# base-board.net
KiCad netlist of a schematic drawn in EAGLE
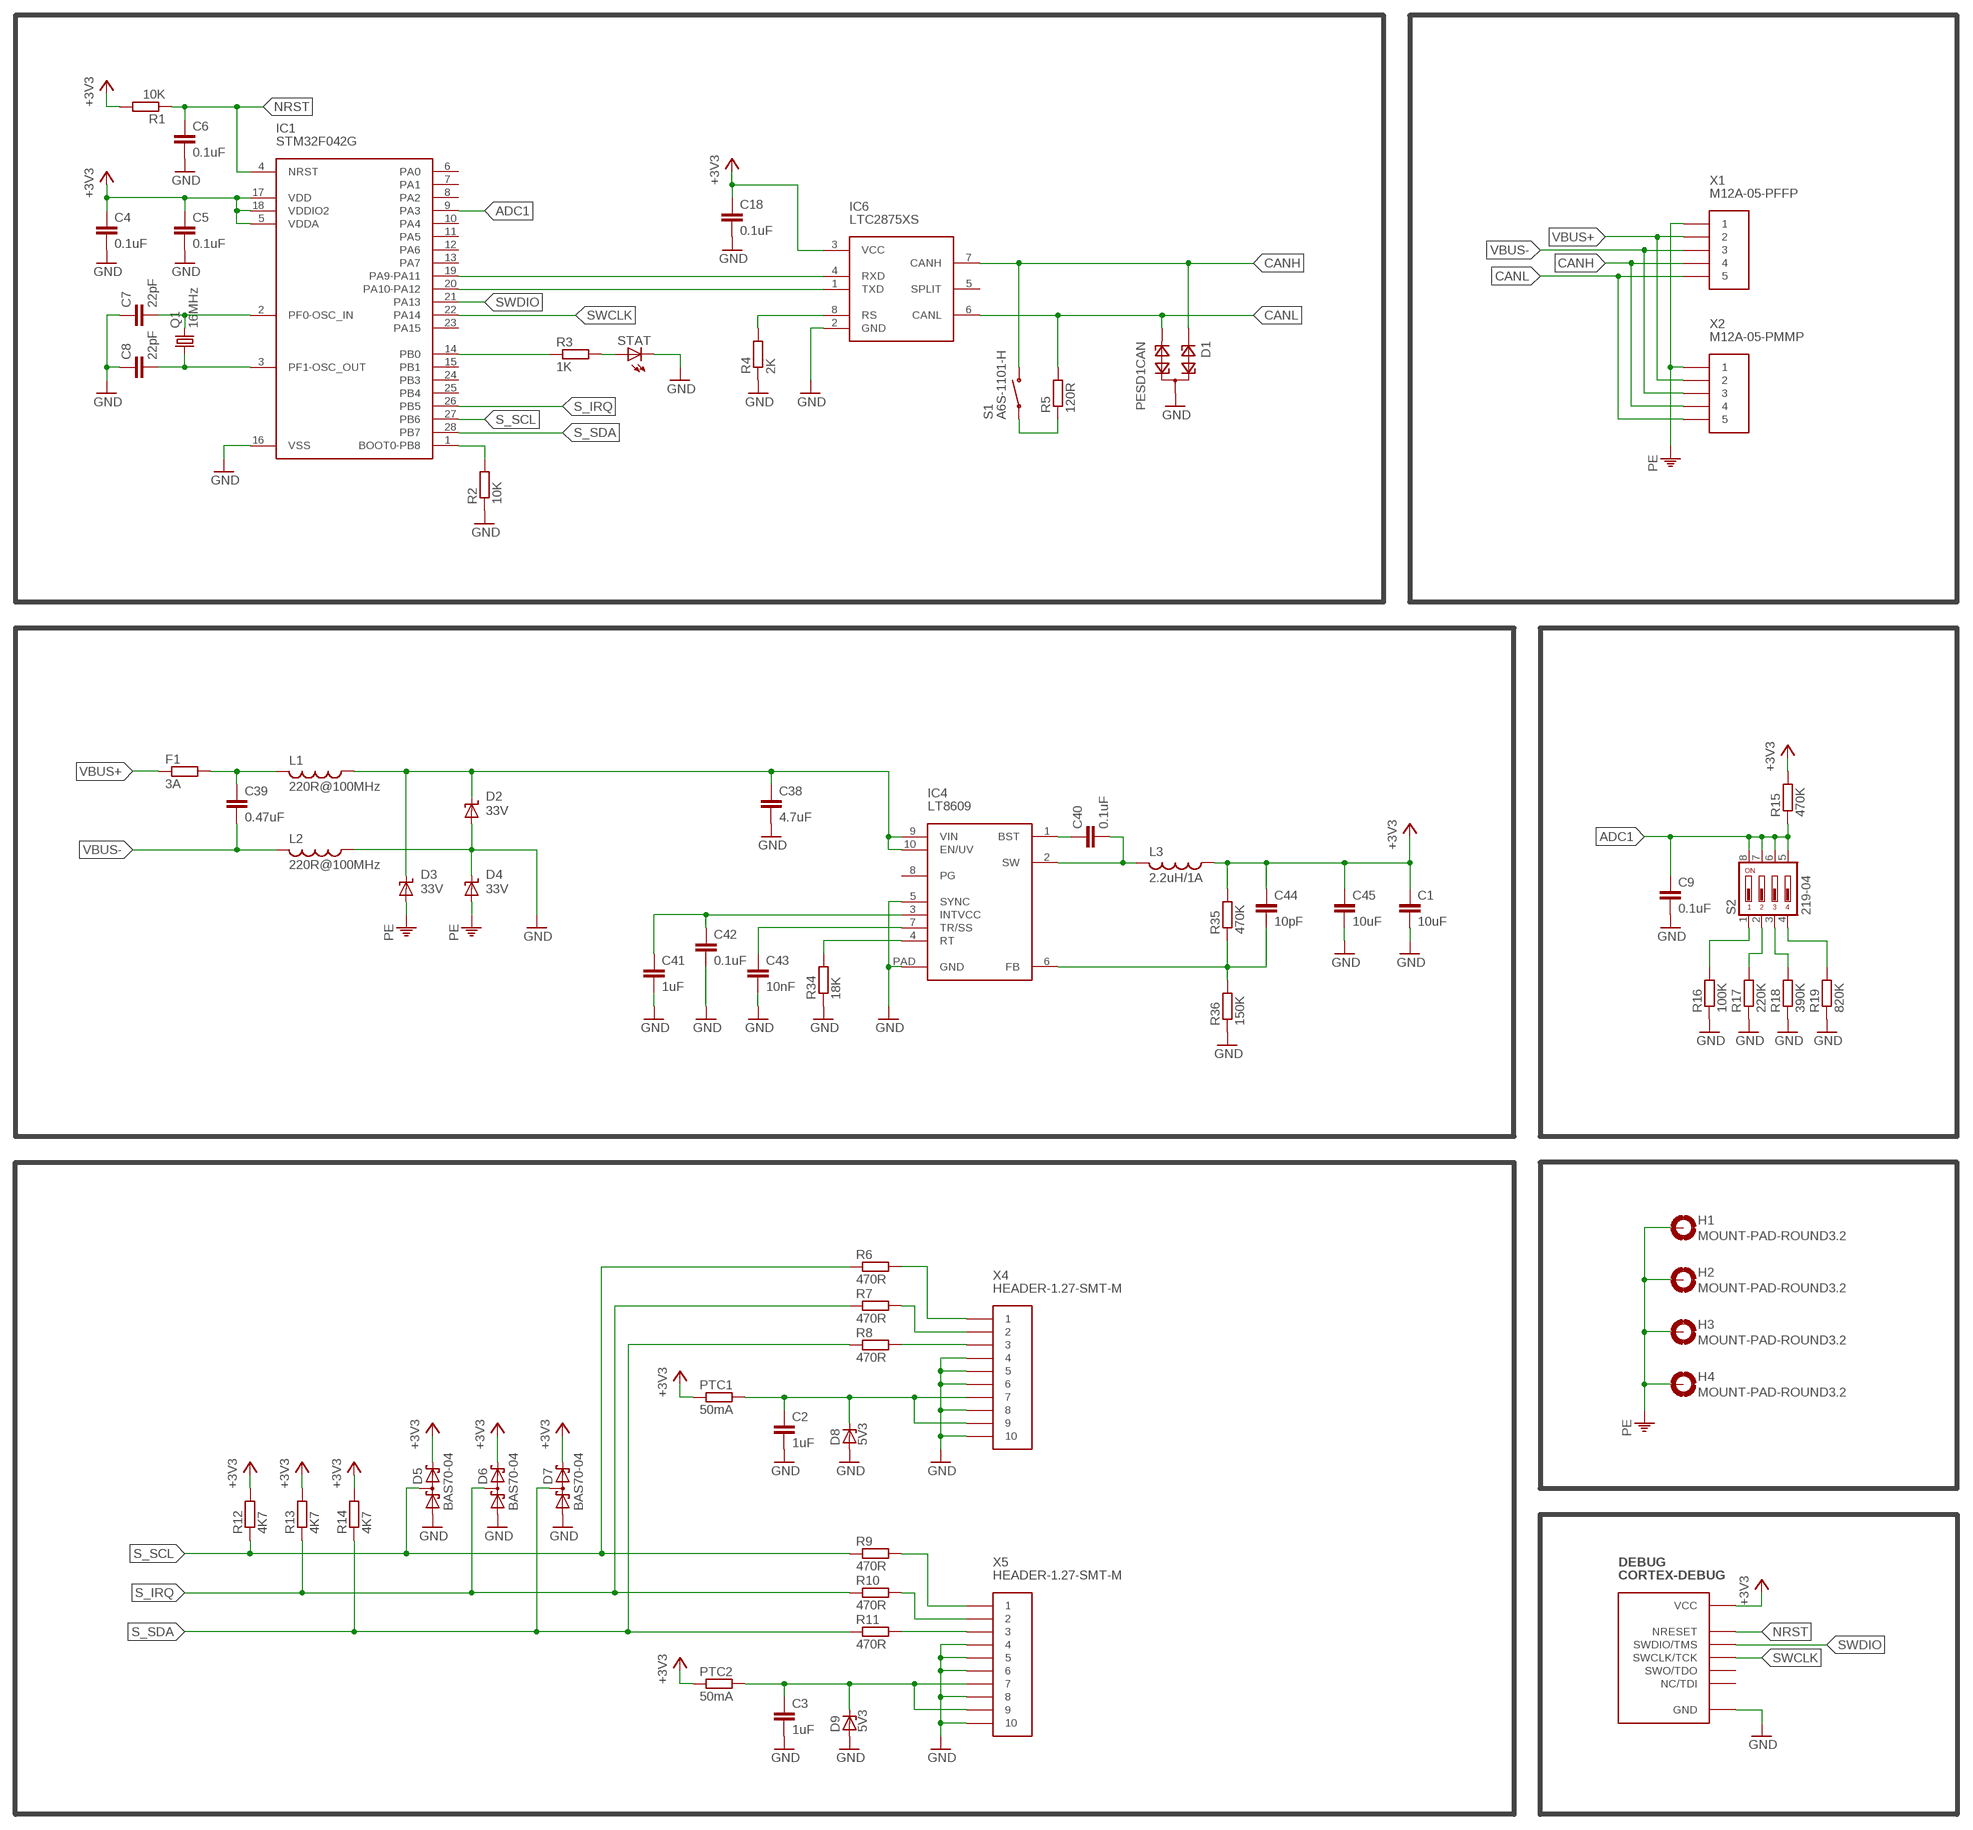
[diagram p0: schematic, sheet 1]

(export (version "E")
  (design (tool "Eeschema 10.0.6"))
  (components
    (comp (ref "C1")
      (value "10uF")
      (footprint "eagle-import:C1206")
      (libsource (lib "eagle-import") (part "C-EUC1206"))
    )
    (comp (ref "C2")
      (value "1uF")
      (footprint "eagle-import:C0603")
      (libsource (lib "eagle-import") (part "C-EUC0603"))
    )
    (comp (ref "C3")
      (value "1uF")
      (footprint "eagle-import:C0603")
      (libsource (lib "eagle-import") (part "C-EUC0603"))
    )
    (comp (ref "C4")
      (value "0.1uF")
      (footprint "eagle-import:C0603")
      (libsource (lib "eagle-import") (part "C-EUC0603"))
    )
    (comp (ref "C5")
      (value "0.1uF")
      (footprint "eagle-import:C0603")
      (libsource (lib "eagle-import") (part "C-EUC0603"))
    )
    (comp (ref "C6")
      (value "0.1uF")
      (footprint "eagle-import:C0603")
      (libsource (lib "eagle-import") (part "C-EUC0603"))
    )
    (comp (ref "C7")
      (value "22pF")
      (footprint "eagle-import:C0603")
      (libsource (lib "eagle-import") (part "C-EUC0603"))
    )
    (comp (ref "C8")
      (value "22pF")
      (footprint "eagle-import:C0603")
      (libsource (lib "eagle-import") (part "C-EUC0603"))
    )
    (comp (ref "C9")
      (value "0.1uF")
      (footprint "eagle-import:C0603")
      (libsource (lib "eagle-import") (part "C-EUC0603"))
    )
    (comp (ref "C18")
      (value "0.1uF")
      (footprint "eagle-import:C0603")
      (libsource (lib "eagle-import") (part "C-EUC0603"))
    )
    (comp (ref "C38")
      (value "4.7uF")
      (footprint "eagle-import:C1206")
      (libsource (lib "eagle-import") (part "C-EUC1206"))
    )
    (comp (ref "C39")
      (value "0.47uF")
      (footprint "eagle-import:C1206")
      (libsource (lib "eagle-import") (part "C-EUC1206"))
    )
    (comp (ref "C40")
      (value "0.1uF")
      (footprint "eagle-import:C0603")
      (libsource (lib "eagle-import") (part "C-EUC0603"))
    )
    (comp (ref "C41")
      (value "1uF")
      (footprint "eagle-import:C0603")
      (libsource (lib "eagle-import") (part "C-EUC0603"))
    )
    (comp (ref "C42")
      (value "0.1uF")
      (footprint "eagle-import:C0603")
      (libsource (lib "eagle-import") (part "C-EUC0603"))
    )
    (comp (ref "C43")
      (value "10nF")
      (footprint "eagle-import:C0603")
      (libsource (lib "eagle-import") (part "C-EUC0603"))
    )
    (comp (ref "C44")
      (value "10pF")
      (footprint "eagle-import:C0603")
      (libsource (lib "eagle-import") (part "C-EUC0603"))
    )
    (comp (ref "C45")
      (value "10uF")
      (footprint "eagle-import:C1206")
      (libsource (lib "eagle-import") (part "C-EUC1206"))
    )
    (comp (ref "D1")
      (value "PESD1CAN")
      (footprint "eagle-import:SOT23")
      (libsource (lib "eagle-import") (part "PESD1CAN"))
    )
    (comp (ref "D2")
      (value "33V")
      (footprint "eagle-import:SMBJ")
      (libsource (lib "eagle-import") (part "SUPPRESSOR-SMBJ"))
    )
    (comp (ref "D3")
      (value "33V")
      (footprint "eagle-import:SMBJ")
      (libsource (lib "eagle-import") (part "SUPPRESSOR-SMBJ"))
    )
    (comp (ref "D4")
      (value "33V")
      (footprint "eagle-import:SMBJ")
      (libsource (lib "eagle-import") (part "SUPPRESSOR-SMBJ"))
    )
    (comp (ref "D5")
      (value "BAS70-04")
      (footprint "eagle-import:SOT23")
      (libsource (lib "eagle-import") (part "BAS70-04"))
    )
    (comp (ref "D6")
      (value "BAS70-04")
      (footprint "eagle-import:SOT23")
      (libsource (lib "eagle-import") (part "BAS70-04"))
    )
    (comp (ref "D7")
      (value "BAS70-04")
      (footprint "eagle-import:SOT23")
      (libsource (lib "eagle-import") (part "BAS70-04"))
    )
    (comp (ref "D8")
      (value "5V3")
      (footprint "eagle-import:SOT23")
      (libsource (lib "eagle-import") (part "ZENER-DIODESOT23"))
    )
    (comp (ref "D9")
      (value "5V3")
      (footprint "eagle-import:SOT23")
      (libsource (lib "eagle-import") (part "ZENER-DIODESOT23"))
    )
    (comp (ref "DEBUG")
      (value "CORTEX-DEBUG")
      (footprint "eagle-import:CORTEX-DEBUG")
      (libsource (lib "eagle-import") (part "CORTEX-DEBUG"))
    )
    (comp (ref "F1")
      (value "3A")
      (footprint "eagle-import:R0805")
      (libsource (lib "eagle-import") (part "R-EU_R0805"))
    )
    (comp (ref "H1")
      (value "MOUNT-PAD-ROUND3.2")
      (footprint "eagle-import:3,2-PAD")
      (libsource (lib "eagle-import") (part "MOUNT-PAD-ROUND3.2"))
    )
    (comp (ref "H2")
      (value "MOUNT-PAD-ROUND3.2")
      (footprint "eagle-import:3,2-PAD")
      (libsource (lib "eagle-import") (part "MOUNT-PAD-ROUND3.2"))
    )
    (comp (ref "H3")
      (value "MOUNT-PAD-ROUND3.2")
      (footprint "eagle-import:3,2-PAD")
      (libsource (lib "eagle-import") (part "MOUNT-PAD-ROUND3.2"))
    )
    (comp (ref "H4")
      (value "MOUNT-PAD-ROUND3.2")
      (footprint "eagle-import:3,2-PAD")
      (libsource (lib "eagle-import") (part "MOUNT-PAD-ROUND3.2"))
    )
    (comp (ref "IC1")
      (value "STM32F042G")
      (footprint "eagle-import:UFQFPN28")
      (libsource (lib "eagle-import") (part "STM32F042G"))
    )
    (comp (ref "IC4")
      (value "LT8609")
      (footprint "eagle-import:MSOP10-PAD")
      (libsource (lib "eagle-import") (part "LT8609"))
    )
    (comp (ref "IC6")
      (value "LTC2875XS")
      (footprint "eagle-import:SOIC8")
      (libsource (lib "eagle-import") (part "LTC2875XS"))
    )
    (comp (ref "L1")
      (value "220R@100MHz")
      (footprint "eagle-import:L3216C")
      (libsource (lib "eagle-import") (part "L-USL3216C"))
    )
    (comp (ref "L2")
      (value "220R@100MHz")
      (footprint "eagle-import:L3216C")
      (libsource (lib "eagle-import") (part "L-USL3216C"))
    )
    (comp (ref "L3")
      (value "2.2uH/1A")
      (footprint "eagle-import:L3216C")
      (libsource (lib "eagle-import") (part "L-USL3216C"))
    )
    (comp (ref "PTC1")
      (value "50mA")
      (footprint "eagle-import:R1206")
      (libsource (lib "eagle-import") (part "R-EU_R1206"))
    )
    (comp (ref "PTC2")
      (value "50mA")
      (footprint "eagle-import:R1206")
      (libsource (lib "eagle-import") (part "R-EU_R1206"))
    )
    (comp (ref "Q1")
      (value "16MHz")
      (footprint "eagle-import:XTAL_3225")
      (libsource (lib "eagle-import") (part "XO_3225"))
    )
    (comp (ref "R1")
      (value "10K")
      (footprint "eagle-import:R0603")
      (libsource (lib "eagle-import") (part "R-EU_R0603"))
    )
    (comp (ref "R2")
      (value "10K")
      (footprint "eagle-import:R0603")
      (libsource (lib "eagle-import") (part "R-EU_R0603"))
    )
    (comp (ref "R3")
      (value "1K")
      (footprint "eagle-import:R0603")
      (libsource (lib "eagle-import") (part "R-EU_R0603"))
    )
    (comp (ref "R4")
      (value "2K")
      (footprint "eagle-import:R0603")
      (libsource (lib "eagle-import") (part "R-EU_R0603"))
    )
    (comp (ref "R5")
      (value "120R")
      (footprint "eagle-import:R0603")
      (libsource (lib "eagle-import") (part "R-EU_R0603"))
    )
    (comp (ref "R6")
      (value "470R")
      (footprint "eagle-import:R0603")
      (libsource (lib "eagle-import") (part "R-EU_R0603"))
    )
    (comp (ref "R7")
      (value "470R")
      (footprint "eagle-import:R0603")
      (libsource (lib "eagle-import") (part "R-EU_R0603"))
    )
    (comp (ref "R8")
      (value "470R")
      (footprint "eagle-import:R0603")
      (libsource (lib "eagle-import") (part "R-EU_R0603"))
    )
    (comp (ref "R9")
      (value "470R")
      (footprint "eagle-import:R0603")
      (libsource (lib "eagle-import") (part "R-EU_R0603"))
    )
    (comp (ref "R10")
      (value "470R")
      (footprint "eagle-import:R0603")
      (libsource (lib "eagle-import") (part "R-EU_R0603"))
    )
    (comp (ref "R11")
      (value "470R")
      (footprint "eagle-import:R0603")
      (libsource (lib "eagle-import") (part "R-EU_R0603"))
    )
    (comp (ref "R12")
      (value "4K7")
      (footprint "eagle-import:R0603")
      (libsource (lib "eagle-import") (part "R-EU_R0603"))
    )
    (comp (ref "R13")
      (value "4K7")
      (footprint "eagle-import:R0603")
      (libsource (lib "eagle-import") (part "R-EU_R0603"))
    )
    (comp (ref "R14")
      (value "4K7")
      (footprint "eagle-import:R0603")
      (libsource (lib "eagle-import") (part "R-EU_R0603"))
    )
    (comp (ref "R15")
      (value "470K")
      (footprint "eagle-import:R0603")
      (libsource (lib "eagle-import") (part "R-EU_R0603"))
    )
    (comp (ref "R16")
      (value "100K")
      (footprint "eagle-import:R0603")
      (libsource (lib "eagle-import") (part "R-EU_R0603"))
    )
    (comp (ref "R17")
      (value "220K")
      (footprint "eagle-import:R0603")
      (libsource (lib "eagle-import") (part "R-EU_R0603"))
    )
    (comp (ref "R18")
      (value "390K")
      (footprint "eagle-import:R0603")
      (libsource (lib "eagle-import") (part "R-EU_R0603"))
    )
    (comp (ref "R19")
      (value "820K")
      (footprint "eagle-import:R0603")
      (libsource (lib "eagle-import") (part "R-EU_R0603"))
    )
    (comp (ref "R34")
      (value "18K")
      (footprint "eagle-import:R0603")
      (libsource (lib "eagle-import") (part "R-EU_R0603"))
    )
    (comp (ref "R35")
      (value "470K")
      (footprint "eagle-import:R0603")
      (libsource (lib "eagle-import") (part "R-EU_R0603"))
    )
    (comp (ref "R36")
      (value "150K")
      (footprint "eagle-import:R0603")
      (libsource (lib "eagle-import") (part "R-EU_R0603"))
    )
    (comp (ref "S1")
      (value "A6S-1101-H")
      (footprint "eagle-import:A6S-1")
      (libsource (lib "eagle-import") (part "A6S-1101-H"))
    )
    (comp (ref "S2")
      (value "219-04")
      (footprint "eagle-import:CTS-219-04")
      (libsource (lib "eagle-import") (part "219-04"))
    )
    (comp (ref "STAT")
      (value "LEDCHIPLED_0805")
      (footprint "eagle-import:CHIPLED_0805")
      (libsource (lib "eagle-import") (part "LEDCHIPLED_0805"))
    )
    (comp (ref "X1")
      (value "M12A-05-PFFP")
      (footprint "eagle-import:AMP-M12A-05-PFFP")
      (libsource (lib "eagle-import") (part "M12A-05-PFFP"))
    )
    (comp (ref "X2")
      (value "M12A-05-PMMP")
      (footprint "eagle-import:AMP-M12A-05-PMMP")
      (libsource (lib "eagle-import") (part "M12A-05-PMMP"))
    )
    (comp (ref "X4")
      (value "HEADER-1.27-SMT-M")
      (footprint "eagle-import:HEADER-1.27-SMT-M")
      (libsource (lib "eagle-import") (part "HEADER-1.27-SMT-M"))
    )
    (comp (ref "X5")
      (value "HEADER-1.27-SMT-M")
      (footprint "eagle-import:HEADER-1.27-SMT-M")
      (libsource (lib "eagle-import") (part "HEADER-1.27-SMT-M"))
    )
  )
  (nets
    (net (code "1") (name "+3V3") (class "Default")
      (node (ref "C1") (pin "1") (pinfunction "1_1") (pintype "passive"))
      (node (ref "C18") (pin "1") (pinfunction "1_1") (pintype "passive"))
      (node (ref "C4") (pin "1") (pinfunction "1_1") (pintype "passive"))
      (node (ref "C44") (pin "1") (pinfunction "1_1") (pintype "passive"))
      (node (ref "C45") (pin "1") (pinfunction "1_1") (pintype "passive"))
      (node (ref "C5") (pin "1") (pinfunction "1_1") (pintype "passive"))
      (node (ref "D5") (pin "2") (pinfunction "C2_2") (pintype "passive"))
      (node (ref "D6") (pin "2") (pinfunction "C2_2") (pintype "passive"))
      (node (ref "D7") (pin "2") (pinfunction "C2_2") (pintype "passive"))
      (node (ref "DEBUG") (pin "VCC") (pinfunction "VCC_VCC") (pintype "bidirectional"))
      (node (ref "IC1") (pin "17") (pinfunction "VDD_17") (pintype "bidirectional"))
      (node (ref "IC1") (pin "18") (pinfunction "VDDIO2_18") (pintype "bidirectional"))
      (node (ref "IC1") (pin "5") (pinfunction "VDDA_5") (pintype "bidirectional"))
      (node (ref "IC6") (pin "3") (pinfunction "VCC_3") (pintype "bidirectional"))
      (node (ref "L3") (pin "1") (pinfunction "1_1") (pintype "passive"))
      (node (ref "PTC1") (pin "1") (pinfunction "1_1") (pintype "passive"))
      (node (ref "PTC2") (pin "1") (pinfunction "1_1") (pintype "passive"))
      (node (ref "R1") (pin "2") (pinfunction "2_2") (pintype "passive"))
      (node (ref "R12") (pin "2") (pinfunction "2_2") (pintype "passive"))
      (node (ref "R13") (pin "2") (pinfunction "2_2") (pintype "passive"))
      (node (ref "R14") (pin "2") (pinfunction "2_2") (pintype "passive"))
      (node (ref "R15") (pin "2") (pinfunction "2_2") (pintype "passive"))
      (node (ref "R35") (pin "2") (pinfunction "2_2") (pintype "passive"))
    )
    (net (code "2") (name "ADC1") (class "Default")
      (node (ref "C9") (pin "1") (pinfunction "1_1") (pintype "passive"))
      (node (ref "IC1") (pin "9") (pinfunction "PA3_9") (pintype "bidirectional"))
      (node (ref "R15") (pin "1") (pinfunction "1_1") (pintype "passive"))
      (node (ref "S2") (pin "5") (pinfunction "5_5") (pintype "passive"))
      (node (ref "S2") (pin "6") (pinfunction "6_6") (pintype "passive"))
      (node (ref "S2") (pin "7") (pinfunction "7_7") (pintype "passive"))
      (node (ref "S2") (pin "8") (pinfunction "8_8") (pintype "passive"))
    )
    (net (code "3") (name "CANH") (class "Default")
      (node (ref "D1") (pin "1") (pinfunction "1_1") (pintype "passive"))
      (node (ref "IC6") (pin "7") (pinfunction "CANH_7") (pintype "bidirectional"))
      (node (ref "S1") (pin "1B") (pinfunction "B_1B") (pintype "bidirectional"))
      (node (ref "X1") (pin "4") (pinfunction "4_4") (pintype "bidirectional"))
      (node (ref "X2") (pin "4") (pinfunction "4_4") (pintype "bidirectional"))
    )
    (net (code "4") (name "CANL") (class "Default")
      (node (ref "D1") (pin "2") (pinfunction "2_2") (pintype "passive"))
      (node (ref "IC6") (pin "6") (pinfunction "CANL_6") (pintype "bidirectional"))
      (node (ref "R5") (pin "2") (pinfunction "2_2") (pintype "passive"))
      (node (ref "X1") (pin "5") (pinfunction "5_5") (pintype "bidirectional"))
      (node (ref "X2") (pin "5") (pinfunction "5_5") (pintype "bidirectional"))
    )
    (net (code "5") (name "GND") (class "Default")
      (node (ref "C1") (pin "2") (pinfunction "2_2") (pintype "passive"))
      (node (ref "C18") (pin "2") (pinfunction "2_2") (pintype "passive"))
      (node (ref "C2") (pin "2") (pinfunction "2_2") (pintype "passive"))
      (node (ref "C3") (pin "2") (pinfunction "2_2") (pintype "passive"))
      (node (ref "C38") (pin "2") (pinfunction "2_2") (pintype "passive"))
      (node (ref "C4") (pin "2") (pinfunction "2_2") (pintype "passive"))
      (node (ref "C41") (pin "2") (pinfunction "2_2") (pintype "passive"))
      (node (ref "C42") (pin "2") (pinfunction "2_2") (pintype "passive"))
      (node (ref "C43") (pin "2") (pinfunction "2_2") (pintype "passive"))
      (node (ref "C45") (pin "2") (pinfunction "2_2") (pintype "passive"))
      (node (ref "C5") (pin "2") (pinfunction "2_2") (pintype "passive"))
      (node (ref "C6") (pin "2") (pinfunction "2_2") (pintype "passive"))
      (node (ref "C7") (pin "1") (pinfunction "1_1") (pintype "passive"))
      (node (ref "C8") (pin "1") (pinfunction "1_1") (pintype "passive"))
      (node (ref "C9") (pin "2") (pinfunction "2_2") (pintype "passive"))
      (node (ref "D1") (pin "3") (pinfunction "3_3") (pintype "passive"))
      (node (ref "D2") (pin "A") (pinfunction "A_A") (pintype "passive"))
      (node (ref "D4") (pin "C") (pinfunction "C_C") (pintype "passive"))
      (node (ref "D5") (pin "1") (pinfunction "A1_1") (pintype "passive"))
      (node (ref "D6") (pin "1") (pinfunction "A1_1") (pintype "passive"))
      (node (ref "D7") (pin "1") (pinfunction "A1_1") (pintype "passive"))
      (node (ref "D8") (pin "1") (pinfunction "A_1") (pintype "passive"))
      (node (ref "D9") (pin "1") (pinfunction "A_1") (pintype "passive"))
      (node (ref "DEBUG") (pin "GND1") (pinfunction "GND_GND1") (pintype "bidirectional"))
      (node (ref "DEBUG") (pin "GND2") (pinfunction "GND_GND2") (pintype "bidirectional"))
      (node (ref "DEBUG") (pin "GND_DETECT") (pinfunction "GND_GND_DETECT") (pintype "bidirectional"))
      (node (ref "IC1") (pin "16") (pinfunction "VSS_16") (pintype "bidirectional"))
      (node (ref "IC4") (pin "5") (pinfunction "SYNC_5") (pintype "bidirectional"))
      (node (ref "IC4") (pin "PAD") (pinfunction "GND_PAD") (pintype "bidirectional"))
      (node (ref "IC6") (pin "2") (pinfunction "GND_2") (pintype "bidirectional"))
      (node (ref "L2") (pin "1") (pinfunction "1_1") (pintype "passive"))
      (node (ref "R16") (pin "1") (pinfunction "1_1") (pintype "passive"))
      (node (ref "R17") (pin "1") (pinfunction "1_1") (pintype "passive"))
      (node (ref "R18") (pin "1") (pinfunction "1_1") (pintype "passive"))
      (node (ref "R19") (pin "1") (pinfunction "1_1") (pintype "passive"))
      (node (ref "R2") (pin "1") (pinfunction "1_1") (pintype "passive"))
      (node (ref "R34") (pin "1") (pinfunction "1_1") (pintype "passive"))
      (node (ref "R36") (pin "1") (pinfunction "1_1") (pintype "passive"))
      (node (ref "R4") (pin "1") (pinfunction "1_1") (pintype "passive"))
      (node (ref "STAT") (pin "C") (pinfunction "C_C") (pintype "passive"))
      (node (ref "X4") (pin "10") (pinfunction "10_10") (pintype "bidirectional"))
      (node (ref "X4") (pin "4") (pinfunction "4_4") (pintype "bidirectional"))
      (node (ref "X4") (pin "5") (pinfunction "5_5") (pintype "bidirectional"))
      (node (ref "X4") (pin "6") (pinfunction "6_6") (pintype "bidirectional"))
      (node (ref "X4") (pin "8") (pinfunction "8_8") (pintype "bidirectional"))
      (node (ref "X5") (pin "10") (pinfunction "10_10") (pintype "bidirectional"))
      (node (ref "X5") (pin "4") (pinfunction "4_4") (pintype "bidirectional"))
      (node (ref "X5") (pin "5") (pinfunction "5_5") (pintype "bidirectional"))
      (node (ref "X5") (pin "6") (pinfunction "6_6") (pintype "bidirectional"))
      (node (ref "X5") (pin "8") (pinfunction "8_8") (pintype "bidirectional"))
    )
    (net (code "6") (name "NRST") (class "Default")
      (node (ref "C6") (pin "1") (pinfunction "1_1") (pintype "passive"))
      (node (ref "DEBUG") (pin "NRESET") (pinfunction "NRESET_NRESET") (pintype "bidirectional"))
      (node (ref "IC1") (pin "4") (pinfunction "NRST_4") (pintype "bidirectional"))
      (node (ref "R1") (pin "1") (pinfunction "1_1") (pintype "passive"))
    )
    (net (code "7") (name "Net-(C39-Pad1)") (class "Default")
      (node (ref "C39") (pin "1") (pinfunction "1_1") (pintype "passive"))
      (node (ref "F1") (pin "2") (pinfunction "2_2") (pintype "passive"))
      (node (ref "L1") (pin "2") (pinfunction "2_2") (pintype "passive"))
    )
    (net (code "8") (name "Net-(D8-C)") (class "Default")
      (node (ref "C2") (pin "1") (pinfunction "1_1") (pintype "passive"))
      (node (ref "D8") (pin "3") (pinfunction "C_3") (pintype "passive"))
      (node (ref "PTC1") (pin "2") (pinfunction "2_2") (pintype "passive"))
      (node (ref "X4") (pin "7") (pinfunction "7_7") (pintype "bidirectional"))
      (node (ref "X4") (pin "9") (pinfunction "9_9") (pintype "bidirectional"))
    )
    (net (code "9") (name "Net-(D9-C)") (class "Default")
      (node (ref "C3") (pin "1") (pinfunction "1_1") (pintype "passive"))
      (node (ref "D9") (pin "3") (pinfunction "C_3") (pintype "passive"))
      (node (ref "PTC2") (pin "2") (pinfunction "2_2") (pintype "passive"))
      (node (ref "X5") (pin "7") (pinfunction "7_7") (pintype "bidirectional"))
      (node (ref "X5") (pin "9") (pinfunction "9_9") (pintype "bidirectional"))
    )
    (net (code "10") (name "Net-(IC1-BOOT0-PB8)") (class "Default")
      (node (ref "IC1") (pin "1") (pinfunction "BOOT0-PB8_1") (pintype "bidirectional"))
      (node (ref "R2") (pin "2") (pinfunction "2_2") (pintype "passive"))
    )
    (net (code "11") (name "Net-(IC1-PA9-PA11)") (class "Default")
      (node (ref "IC1") (pin "19") (pinfunction "PA9-PA11_19") (pintype "bidirectional"))
      (node (ref "IC6") (pin "4") (pinfunction "RXD_4") (pintype "bidirectional"))
    )
    (net (code "12") (name "Net-(IC1-PA10-PA12)") (class "Default")
      (node (ref "IC1") (pin "20") (pinfunction "PA10-PA12_20") (pintype "bidirectional"))
      (node (ref "IC6") (pin "1") (pinfunction "TXD_1") (pintype "bidirectional"))
    )
    (net (code "13") (name "Net-(IC1-PB0)") (class "Default")
      (node (ref "IC1") (pin "14") (pinfunction "PB0_14") (pintype "bidirectional"))
      (node (ref "R3") (pin "1") (pinfunction "1_1") (pintype "passive"))
    )
    (net (code "14") (name "Net-(IC1-PF0-OSC_IN)") (class "Default")
      (node (ref "C7") (pin "2") (pinfunction "2_2") (pintype "passive"))
      (node (ref "IC1") (pin "2") (pinfunction "PF0-OSC_IN_2") (pintype "bidirectional"))
      (node (ref "Q1") (pin "3") (pinfunction "2_3") (pintype "passive"))
    )
    (net (code "15") (name "Net-(IC1-PF1-OSC_OUT)") (class "Default")
      (node (ref "C8") (pin "2") (pinfunction "2_2") (pintype "passive"))
      (node (ref "IC1") (pin "3") (pinfunction "PF1-OSC_OUT_3") (pintype "bidirectional"))
      (node (ref "Q1") (pin "1") (pinfunction "1_1") (pintype "passive"))
    )
    (net (code "16") (name "Net-(IC4-BST)") (class "Default")
      (node (ref "C40") (pin "1") (pinfunction "1_1") (pintype "passive"))
      (node (ref "IC4") (pin "1") (pinfunction "BST_1") (pintype "bidirectional"))
    )
    (net (code "17") (name "Net-(IC4-EN{slash}UV)") (class "Default")
      (node (ref "C38") (pin "1") (pinfunction "1_1") (pintype "passive"))
      (node (ref "D2") (pin "C") (pinfunction "C_C") (pintype "passive"))
      (node (ref "D3") (pin "C") (pinfunction "C_C") (pintype "passive"))
      (node (ref "IC4") (pin "10") (pinfunction "EN/UV_10") (pintype "bidirectional"))
      (node (ref "IC4") (pin "9") (pinfunction "VIN_9") (pintype "bidirectional"))
      (node (ref "L1") (pin "1") (pinfunction "1_1") (pintype "passive"))
    )
    (net (code "18") (name "Net-(IC4-FB)") (class "Default")
      (node (ref "C44") (pin "2") (pinfunction "2_2") (pintype "passive"))
      (node (ref "IC4") (pin "6") (pinfunction "FB_6") (pintype "bidirectional"))
      (node (ref "R35") (pin "1") (pinfunction "1_1") (pintype "passive"))
      (node (ref "R36") (pin "2") (pinfunction "2_2") (pintype "passive"))
    )
    (net (code "19") (name "Net-(IC4-INTVCC)") (class "Default")
      (node (ref "C41") (pin "1") (pinfunction "1_1") (pintype "passive"))
      (node (ref "C42") (pin "1") (pinfunction "1_1") (pintype "passive"))
      (node (ref "IC4") (pin "3") (pinfunction "INTVCC_3") (pintype "bidirectional"))
    )
    (net (code "20") (name "Net-(IC4-RT)") (class "Default")
      (node (ref "IC4") (pin "4") (pinfunction "RT_4") (pintype "bidirectional"))
      (node (ref "R34") (pin "2") (pinfunction "2_2") (pintype "passive"))
    )
    (net (code "21") (name "Net-(IC4-SW)") (class "Default")
      (node (ref "C40") (pin "2") (pinfunction "2_2") (pintype "passive"))
      (node (ref "IC4") (pin "2") (pinfunction "SW_2") (pintype "bidirectional"))
      (node (ref "L3") (pin "2") (pinfunction "2_2") (pintype "passive"))
    )
    (net (code "22") (name "Net-(IC4-TR{slash}SS)") (class "Default")
      (node (ref "C43") (pin "1") (pinfunction "1_1") (pintype "passive"))
      (node (ref "IC4") (pin "7") (pinfunction "TR/SS_7") (pintype "bidirectional"))
    )
    (net (code "23") (name "Net-(IC6-RS)") (class "Default")
      (node (ref "IC6") (pin "8") (pinfunction "RS_8") (pintype "bidirectional"))
      (node (ref "R4") (pin "2") (pinfunction "2_2") (pintype "passive"))
    )
    (net (code "24") (name "Net-(R3-Pad2)") (class "Default")
      (node (ref "R3") (pin "2") (pinfunction "2_2") (pintype "passive"))
      (node (ref "STAT") (pin "A") (pinfunction "A_A") (pintype "passive"))
    )
    (net (code "25") (name "Net-(R6-Pad2)") (class "Default")
      (node (ref "R6") (pin "2") (pinfunction "2_2") (pintype "passive"))
      (node (ref "X4") (pin "1") (pinfunction "1_1") (pintype "bidirectional"))
    )
    (net (code "26") (name "Net-(R7-Pad2)") (class "Default")
      (node (ref "R7") (pin "2") (pinfunction "2_2") (pintype "passive"))
      (node (ref "X4") (pin "2") (pinfunction "2_2") (pintype "bidirectional"))
    )
    (net (code "27") (name "Net-(R8-Pad2)") (class "Default")
      (node (ref "R8") (pin "2") (pinfunction "2_2") (pintype "passive"))
      (node (ref "X4") (pin "3") (pinfunction "3_3") (pintype "bidirectional"))
    )
    (net (code "28") (name "Net-(R9-Pad2)") (class "Default")
      (node (ref "R9") (pin "2") (pinfunction "2_2") (pintype "passive"))
      (node (ref "X5") (pin "1") (pinfunction "1_1") (pintype "bidirectional"))
    )
    (net (code "29") (name "Net-(R10-Pad2)") (class "Default")
      (node (ref "R10") (pin "2") (pinfunction "2_2") (pintype "passive"))
      (node (ref "X5") (pin "2") (pinfunction "2_2") (pintype "bidirectional"))
    )
    (net (code "30") (name "Net-(R11-Pad2)") (class "Default")
      (node (ref "R11") (pin "2") (pinfunction "2_2") (pintype "passive"))
      (node (ref "X5") (pin "3") (pinfunction "3_3") (pintype "bidirectional"))
    )
    (net (code "31") (name "Net-(R16-Pad2)") (class "Default")
      (node (ref "R16") (pin "2") (pinfunction "2_2") (pintype "passive"))
      (node (ref "S2") (pin "1") (pinfunction "1_1") (pintype "passive"))
    )
    (net (code "32") (name "Net-(R17-Pad2)") (class "Default")
      (node (ref "R17") (pin "2") (pinfunction "2_2") (pintype "passive"))
      (node (ref "S2") (pin "2") (pinfunction "2_2") (pintype "passive"))
    )
    (net (code "33") (name "Net-(R18-Pad2)") (class "Default")
      (node (ref "R18") (pin "2") (pinfunction "2_2") (pintype "passive"))
      (node (ref "S2") (pin "3") (pinfunction "3_3") (pintype "passive"))
    )
    (net (code "34") (name "Net-(R19-Pad2)") (class "Default")
      (node (ref "R19") (pin "2") (pinfunction "2_2") (pintype "passive"))
      (node (ref "S2") (pin "4") (pinfunction "4_4") (pintype "passive"))
    )
    (net (code "35") (name "Net-(S1-A)") (class "Default")
      (node (ref "R5") (pin "1") (pinfunction "1_1") (pintype "passive"))
      (node (ref "S1") (pin "1A") (pinfunction "A_1A") (pintype "bidirectional"))
    )
    (net (code "36") (name "PE") (class "Default")
      (node (ref "D3") (pin "A") (pinfunction "A_A") (pintype "passive"))
      (node (ref "D4") (pin "A") (pinfunction "A_A") (pintype "passive"))
      (node (ref "H1") (pin "B3,2") (pinfunction "MOUNT_B3,2") (pintype "passive"))
      (node (ref "H2") (pin "B3,2") (pinfunction "MOUNT_B3,2") (pintype "passive"))
      (node (ref "H3") (pin "B3,2") (pinfunction "MOUNT_B3,2") (pintype "passive"))
      (node (ref "H4") (pin "B3,2") (pinfunction "MOUNT_B3,2") (pintype "passive"))
      (node (ref "X1") (pin "1") (pinfunction "1_1") (pintype "bidirectional"))
      (node (ref "X2") (pin "1") (pinfunction "1_1") (pintype "bidirectional"))
    )
    (net (code "37") (name "SWCLK") (class "Default")
      (node (ref "DEBUG") (pin "SWCLK/TCK") (pinfunction "SWCLK/TCK_SWCLK/TCK") (pintype "bidirectional"))
      (node (ref "IC1") (pin "22") (pinfunction "PA14_22") (pintype "bidirectional"))
    )
    (net (code "38") (name "SWDIO") (class "Default")
      (node (ref "DEBUG") (pin "SWDIO/TMS") (pinfunction "SWDIO/TMS_SWDIO/TMS") (pintype "bidirectional"))
      (node (ref "IC1") (pin "21") (pinfunction "PA13_21") (pintype "bidirectional"))
    )
    (net (code "39") (name "S_IRQ") (class "Default")
      (node (ref "D6") (pin "3") (pinfunction "C1A2_3") (pintype "passive"))
      (node (ref "IC1") (pin "26") (pinfunction "PB5_26") (pintype "bidirectional"))
      (node (ref "R10") (pin "1") (pinfunction "1_1") (pintype "passive"))
      (node (ref "R13") (pin "1") (pinfunction "1_1") (pintype "passive"))
      (node (ref "R7") (pin "1") (pinfunction "1_1") (pintype "passive"))
    )
    (net (code "40") (name "S_SCL") (class "Default")
      (node (ref "D5") (pin "3") (pinfunction "C1A2_3") (pintype "passive"))
      (node (ref "IC1") (pin "27") (pinfunction "PB6_27") (pintype "bidirectional"))
      (node (ref "R12") (pin "1") (pinfunction "1_1") (pintype "passive"))
      (node (ref "R6") (pin "1") (pinfunction "1_1") (pintype "passive"))
      (node (ref "R9") (pin "1") (pinfunction "1_1") (pintype "passive"))
    )
    (net (code "41") (name "S_SDA") (class "Default")
      (node (ref "D7") (pin "3") (pinfunction "C1A2_3") (pintype "passive"))
      (node (ref "IC1") (pin "28") (pinfunction "PB7_28") (pintype "bidirectional"))
      (node (ref "R11") (pin "1") (pinfunction "1_1") (pintype "passive"))
      (node (ref "R14") (pin "1") (pinfunction "1_1") (pintype "passive"))
      (node (ref "R8") (pin "1") (pinfunction "1_1") (pintype "passive"))
    )
    (net (code "42") (name "VBUS+") (class "Default")
      (node (ref "F1") (pin "1") (pinfunction "1_1") (pintype "passive"))
      (node (ref "X1") (pin "2") (pinfunction "2_2") (pintype "bidirectional"))
      (node (ref "X2") (pin "2") (pinfunction "2_2") (pintype "bidirectional"))
    )
    (net (code "43") (name "VBUS-") (class "Default")
      (node (ref "C39") (pin "2") (pinfunction "2_2") (pintype "passive"))
      (node (ref "L2") (pin "2") (pinfunction "2_2") (pintype "passive"))
      (node (ref "X1") (pin "3") (pinfunction "3_3") (pintype "bidirectional"))
      (node (ref "X2") (pin "3") (pinfunction "3_3") (pintype "bidirectional"))
    )
    (net (code "44") (name "unconnected-(DEBUG-PadNC{slash}TDI)") (class "Default")
      (node (ref "DEBUG") (pin "NC/TDI") (pinfunction "NC/TDI_NC/TDI") (pintype "bidirectional"))
    )
    (net (code "45") (name "unconnected-(DEBUG-PadSWO{slash}TDO)") (class "Default")
      (node (ref "DEBUG") (pin "SWO/TDO") (pinfunction "SWO/TDO_SWO/TDO") (pintype "bidirectional"))
    )
    (net (code "46") (name "unconnected-(IC1-PA0-Pad6)") (class "Default")
      (node (ref "IC1") (pin "6") (pinfunction "PA0_6") (pintype "bidirectional"))
    )
    (net (code "47") (name "unconnected-(IC1-PA1-Pad7)") (class "Default")
      (node (ref "IC1") (pin "7") (pinfunction "PA1_7") (pintype "bidirectional"))
    )
    (net (code "48") (name "unconnected-(IC1-PA2-Pad8)") (class "Default")
      (node (ref "IC1") (pin "8") (pinfunction "PA2_8") (pintype "bidirectional"))
    )
    (net (code "49") (name "unconnected-(IC1-PA4-Pad10)") (class "Default")
      (node (ref "IC1") (pin "10") (pinfunction "PA4_10") (pintype "bidirectional"))
    )
    (net (code "50") (name "unconnected-(IC1-PA5-Pad11)") (class "Default")
      (node (ref "IC1") (pin "11") (pinfunction "PA5_11") (pintype "bidirectional"))
    )
    (net (code "51") (name "unconnected-(IC1-PA6-Pad12)") (class "Default")
      (node (ref "IC1") (pin "12") (pinfunction "PA6_12") (pintype "bidirectional"))
    )
    (net (code "52") (name "unconnected-(IC1-PA7-Pad13)") (class "Default")
      (node (ref "IC1") (pin "13") (pinfunction "PA7_13") (pintype "bidirectional"))
    )
    (net (code "53") (name "unconnected-(IC1-PA15-Pad23)") (class "Default")
      (node (ref "IC1") (pin "23") (pinfunction "PA15_23") (pintype "bidirectional"))
    )
    (net (code "54") (name "unconnected-(IC1-PB1-Pad15)") (class "Default")
      (node (ref "IC1") (pin "15") (pinfunction "PB1_15") (pintype "bidirectional"))
    )
    (net (code "55") (name "unconnected-(IC1-PB3-Pad24)") (class "Default")
      (node (ref "IC1") (pin "24") (pinfunction "PB3_24") (pintype "bidirectional"))
    )
    (net (code "56") (name "unconnected-(IC1-PB4-Pad25)") (class "Default")
      (node (ref "IC1") (pin "25") (pinfunction "PB4_25") (pintype "bidirectional"))
    )
    (net (code "57") (name "unconnected-(IC4-PG-Pad8)") (class "Default")
      (node (ref "IC4") (pin "8") (pinfunction "PG_8") (pintype "bidirectional"))
    )
    (net (code "58") (name "unconnected-(IC6-SPLIT-Pad5)") (class "Default")
      (node (ref "IC6") (pin "5") (pinfunction "SPLIT_5") (pintype "bidirectional"))
    )
  )
)
